# SD_CARD_Sheet1.net
KiCad netlist of a schematic drawn in Altium Designer
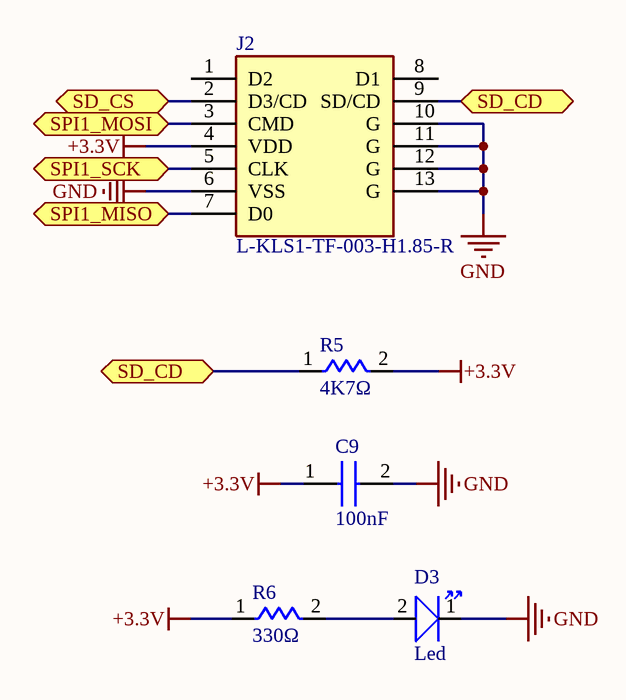
[diagram p0: SD_CARD_Sheet1.SchDoc]

(export (version "E")
  (design (tool "Eeschema 10.0.6"))
  (components
    (comp (ref "C9")
      (value "100nF")
      (footprint "CAP - 0603")
      (description "Capacitor")
      (libsource (lib "Faydali_Yuk_Schlib1") (part "CAP"))
    )
    (comp (ref "D3")
      (value "Led")
      (footprint "LED - 0603")
      (description "HL-PST-1608U51GC - LED SMD 0603 GREEN 500mcd 120° WATER CLEAR")
      (libsource (lib "Faydali_Yuk_Schlib1") (part "Led"))
    )
    (comp (ref "J2")
      (value "L-KLS1-TF-003-H1.85-R")
      (footprint "SD CARD L-KLS1-TF-003-H1.85-R")
      (description "L-KLS1-TF-003-H1.85-R - CONNECTOR MICRO SD CARD SMD KLS")
      (libsource (lib "Faydali_Yuk_Schlib1") (part "SD CARD L-KLS1-TF-003-H1.85-R"))
    )
    (comp (ref "R5")
      (value "4K7Ω")
      (footprint "RES - 0603")
      (description "SMD Res")
      (libsource (lib "Faydali_Yuk_Schlib1") (part "Res"))
    )
    (comp (ref "R6")
      (value "330Ω")
      (footprint "RES - 0603")
      (description "SMD Res")
      (libsource (lib "Faydali_Yuk_Schlib1") (part "Res"))
    )
  )
  (nets
    (net (code "1") (name "+3.3V") (class "Default")
      (node (ref "C9") (pin "1") (pinfunction "1_1") (pintype "passive"))
      (node (ref "J2") (pin "4") (pinfunction "VDD_4") (pintype "passive"))
      (node (ref "R5") (pin "2") (pinfunction "2_2") (pintype "passive"))
      (node (ref "R6") (pin "1") (pinfunction "1_1") (pintype "passive"))
    )
    (net (code "2") (name "/SD_CD") (class "Default")
      (node (ref "J2") (pin "9") (pinfunction "SD/CD_9") (pintype "passive"))
      (node (ref "R5") (pin "1") (pinfunction "1_1") (pintype "passive"))
    )
    (net (code "3") (name "/SD_CS") (class "Default")
      (node (ref "J2") (pin "2") (pinfunction "D3/CD_2") (pintype "passive"))
    )
    (net (code "4") (name "/SPI1_MISO") (class "Default")
      (node (ref "J2") (pin "7") (pinfunction "D0_7") (pintype "passive"))
    )
    (net (code "5") (name "/SPI1_MOSI") (class "Default")
      (node (ref "J2") (pin "3") (pinfunction "CMD_3") (pintype "passive"))
    )
    (net (code "6") (name "/SPI1_SCK") (class "Default")
      (node (ref "J2") (pin "5") (pinfunction "CLK_5") (pintype "passive"))
    )
    (net (code "7") (name "GND") (class "Default")
      (node (ref "C9") (pin "2") (pinfunction "2_2") (pintype "passive"))
      (node (ref "D3") (pin "1") (pinfunction "1_1") (pintype "passive"))
      (node (ref "J2") (pin "10") (pinfunction "G_10") (pintype "passive"))
      (node (ref "J2") (pin "11") (pinfunction "G_11") (pintype "passive"))
      (node (ref "J2") (pin "12") (pinfunction "G_12") (pintype "passive"))
      (node (ref "J2") (pin "13") (pinfunction "G_13") (pintype "passive"))
      (node (ref "J2") (pin "6") (pinfunction "VSS_6") (pintype "passive"))
    )
    (net (code "8") (name "Net-(D3-Pad2)") (class "Default")
      (node (ref "D3") (pin "2") (pinfunction "2_2") (pintype "passive"))
      (node (ref "R6") (pin "2") (pinfunction "2_2") (pintype "passive"))
    )
    (net (code "9") (name "unconnected-(J2-D1-Pad8)") (class "Default")
      (node (ref "J2") (pin "8") (pinfunction "D1_8") (pintype "passive"))
    )
    (net (code "10") (name "unconnected-(J2-D2-Pad1)") (class "Default")
      (node (ref "J2") (pin "1") (pinfunction "D2_1") (pintype "passive"))
    )
  )
)
